# motorized_pinwheel.net
KiCad netlist of a schematic drawn in EAGLE
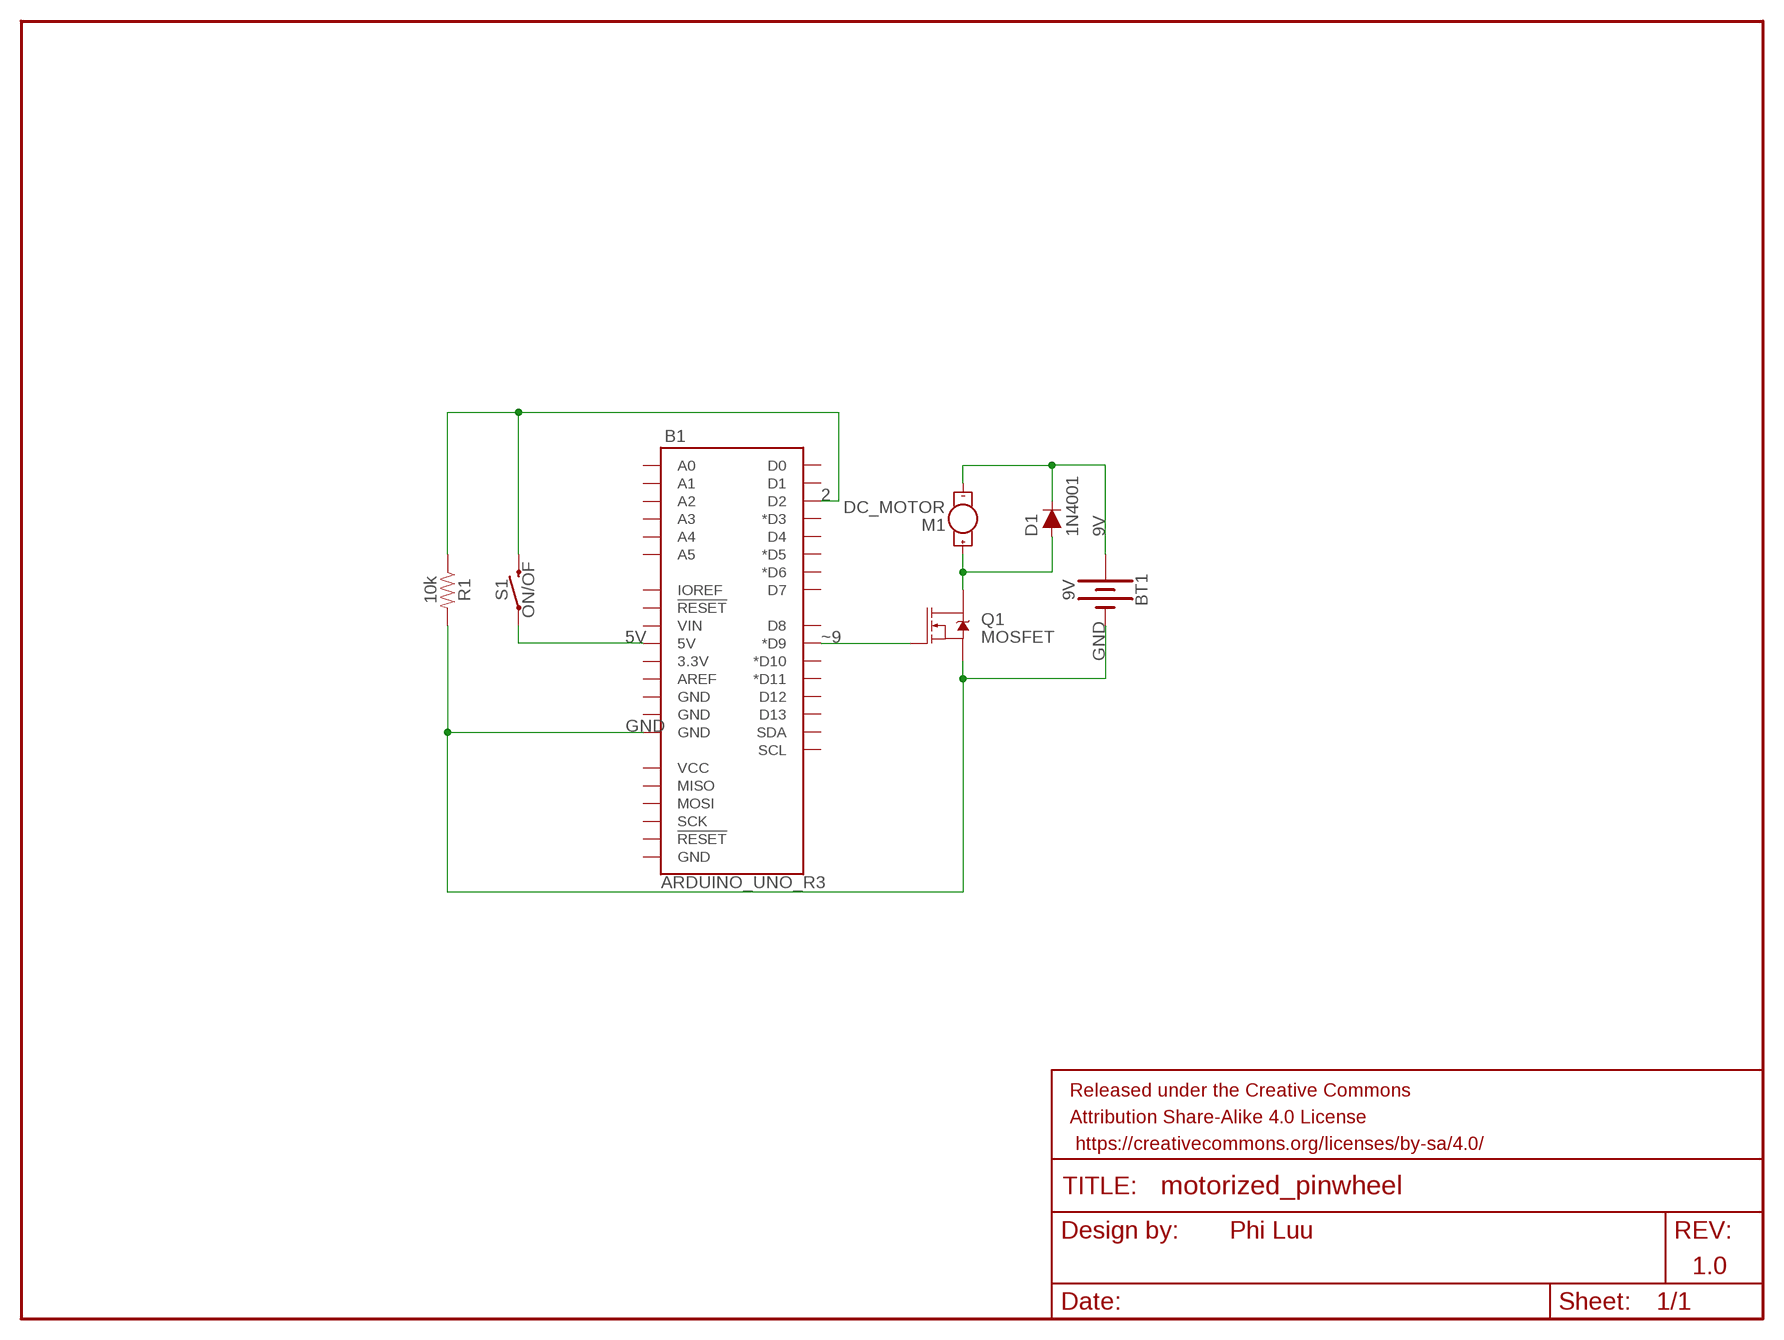
[diagram p0: schematic, sheet 1]

(export (version "E")
  (design (tool "Eeschema 10.0.6"))
  (components
    (comp (ref "B1")
      (value "ARDUINO_UNO_R3")
      (footprint "eagle-import:ARDUINO_R3")
      (libsource (lib "eagle-import") (part "ARDUINO_UNO_R3"))
    )
    (comp (ref "BT1")
      (value "9V")
      (footprint "eagle-import:BATTCON_9V")
      (libsource (lib "eagle-import") (part "BATTERY-9V"))
    )
    (comp (ref "D1")
      (value "1N4001")
      (footprint "eagle-import:DIODE-1N4001")
      (libsource (lib "eagle-import") (part "DIODE-PTH"))
    )
    (comp (ref "FRAME1")
      (value "FRAME-LETTER")
      (footprint "eagle-import:CREATIVE_COMMONS")
      (libsource (lib "eagle-import") (part "FRAME-LETTER"))
    )
    (comp (ref "M1")
      (value "DC_MOTOR")
      (footprint "eagle-import:VIBE-MOTOR-10MM")
      (libsource (lib "eagle-import") (part "MOTOR10MM"))
    )
    (comp (ref "Q1")
      (value "MOSFET")
      (footprint "eagle-import:TO220V")
      (libsource (lib "eagle-import") (part "MOSFET-NCH-FQP30N06L"))
    )
    (comp (ref "R1")
      (value "10k")
      (footprint "eagle-import:AXIAL-0.3")
      (libsource (lib "eagle-import") (part "10KOHM-HORIZ-1/4W-5%"))
    )
    (comp (ref "S1")
      (value "ON/OF")
      (footprint "eagle-import:TACTILE_SWITCH_PTH_6.0MM")
      (libsource (lib "eagle-import") (part "MOMENTARY-SWITCH-SPST-PTH-6.0MM"))
    )
  )
  (nets
    (net (code "1") (name "/2") (class "Default")
      (node (ref "B1") (pin "D2") (pinfunction "D2_D2") (pintype "bidirectional"))
      (node (ref "R1") (pin "P$1") (pinfunction "1_P$1") (pintype "passive"))
      (node (ref "S1") (pin "3") (pinfunction "2_3") (pintype "passive"))
    )
    (net (code "2") (name "/5V") (class "Default")
      (node (ref "B1") (pin "5V") (pinfunction "5V_5V") (pintype "bidirectional"))
      (node (ref "S1") (pin "1") (pinfunction "1_1") (pintype "passive"))
    )
    (net (code "3") (name "/9V") (class "Default")
      (node (ref "BT1") (pin "+") (pinfunction "+_+") (pintype "power_in"))
      (node (ref "D1") (pin "C") (pinfunction "C_C") (pintype "passive"))
      (node (ref "M1") (pin "-") (pinfunction "-_-") (pintype "bidirectional"))
    )
    (net (code "4") (name "/GND") (class "Default")
      (node (ref "B1") (pin "GND@2") (pinfunction "GND_GND@2") (pintype "bidirectional"))
      (node (ref "BT1") (pin "-") (pinfunction "-_-") (pintype "power_in"))
      (node (ref "Q1") (pin "3") (pinfunction "S_3") (pintype "bidirectional"))
      (node (ref "R1") (pin "P$2") (pinfunction "2_P$2") (pintype "passive"))
    )
    (net (code "5") (name "/~{9}") (class "Default")
      (node (ref "B1") (pin "D9") (pinfunction "*D9_D9") (pintype "bidirectional"))
      (node (ref "Q1") (pin "1") (pinfunction "G_1") (pintype "bidirectional"))
    )
    (net (code "6") (name "Net-(Q1-D)") (class "Default")
      (node (ref "D1") (pin "A") (pinfunction "A_A") (pintype "passive"))
      (node (ref "M1") (pin "+") (pinfunction "+_+") (pintype "bidirectional"))
      (node (ref "Q1") (pin "2") (pinfunction "D_2") (pintype "bidirectional"))
    )
    (net (code "7") (name "unconnected-(B1-*D3-PadD3)") (class "Default")
      (node (ref "B1") (pin "D3") (pinfunction "*D3_D3") (pintype "bidirectional"))
    )
    (net (code "8") (name "unconnected-(B1-*D5-PadD5)") (class "Default")
      (node (ref "B1") (pin "D5") (pinfunction "*D5_D5") (pintype "bidirectional"))
    )
    (net (code "9") (name "unconnected-(B1-*D6-PadD6)") (class "Default")
      (node (ref "B1") (pin "D6") (pinfunction "*D6_D6") (pintype "bidirectional"))
    )
    (net (code "10") (name "unconnected-(B1-*D10-PadD10)") (class "Default")
      (node (ref "B1") (pin "D10") (pinfunction "*D10_D10") (pintype "bidirectional"))
    )
    (net (code "11") (name "unconnected-(B1-*D11-PadD11)") (class "Default")
      (node (ref "B1") (pin "D11") (pinfunction "*D11_D11") (pintype "bidirectional"))
    )
    (net (code "12") (name "unconnected-(B1-GND-PadGND@1)") (class "Default")
      (node (ref "B1") (pin "GND@1") (pinfunction "GND_GND@1") (pintype "bidirectional"))
    )
    (net (code "13") (name "unconnected-(B1-GND-PadGND@3)") (class "Default")
      (node (ref "B1") (pin "GND@3") (pinfunction "GND_GND@3") (pintype "bidirectional"))
    )
    (net (code "14") (name "unconnected-(B1-GND-PadGND@4)") (class "Default")
      (node (ref "B1") (pin "GND@4") (pinfunction "GND_GND@4") (pintype "bidirectional"))
    )
    (net (code "15") (name "unconnected-(B1-Pad3.3V)") (class "Default")
      (node (ref "B1") (pin "3.3V") (pinfunction "3.3V_3.3V") (pintype "bidirectional"))
    )
    (net (code "16") (name "unconnected-(B1-PadA0)") (class "Default")
      (node (ref "B1") (pin "A0") (pinfunction "A0_A0") (pintype "bidirectional"))
    )
    (net (code "17") (name "unconnected-(B1-PadA1)") (class "Default")
      (node (ref "B1") (pin "A1") (pinfunction "A1_A1") (pintype "bidirectional"))
    )
    (net (code "18") (name "unconnected-(B1-PadA2)") (class "Default")
      (node (ref "B1") (pin "A2") (pinfunction "A2_A2") (pintype "bidirectional"))
    )
    (net (code "19") (name "unconnected-(B1-PadA3)") (class "Default")
      (node (ref "B1") (pin "A3") (pinfunction "A3_A3") (pintype "bidirectional"))
    )
    (net (code "20") (name "unconnected-(B1-PadA4)") (class "Default")
      (node (ref "B1") (pin "A4") (pinfunction "A4_A4") (pintype "bidirectional"))
    )
    (net (code "21") (name "unconnected-(B1-PadA5)") (class "Default")
      (node (ref "B1") (pin "A5") (pinfunction "A5_A5") (pintype "bidirectional"))
    )
    (net (code "22") (name "unconnected-(B1-PadAREF)") (class "Default")
      (node (ref "B1") (pin "AREF") (pinfunction "AREF_AREF") (pintype "bidirectional"))
    )
    (net (code "23") (name "unconnected-(B1-PadD0)") (class "Default")
      (node (ref "B1") (pin "D0") (pinfunction "D0_D0") (pintype "bidirectional"))
    )
    (net (code "24") (name "unconnected-(B1-PadD1)") (class "Default")
      (node (ref "B1") (pin "D1") (pinfunction "D1_D1") (pintype "bidirectional"))
    )
    (net (code "25") (name "unconnected-(B1-PadD4)") (class "Default")
      (node (ref "B1") (pin "D4") (pinfunction "D4_D4") (pintype "bidirectional"))
    )
    (net (code "26") (name "unconnected-(B1-PadD7)") (class "Default")
      (node (ref "B1") (pin "D7") (pinfunction "D7_D7") (pintype "bidirectional"))
    )
    (net (code "27") (name "unconnected-(B1-PadD8)") (class "Default")
      (node (ref "B1") (pin "D8") (pinfunction "D8_D8") (pintype "bidirectional"))
    )
    (net (code "28") (name "unconnected-(B1-PadD12)") (class "Default")
      (node (ref "B1") (pin "D12") (pinfunction "D12_D12") (pintype "bidirectional"))
    )
    (net (code "29") (name "unconnected-(B1-PadD13)") (class "Default")
      (node (ref "B1") (pin "D13") (pinfunction "D13_D13") (pintype "bidirectional"))
    )
    (net (code "30") (name "unconnected-(B1-PadIOREF)") (class "Default")
      (node (ref "B1") (pin "IOREF") (pinfunction "IOREF_IOREF") (pintype "bidirectional"))
    )
    (net (code "31") (name "unconnected-(B1-PadMISO)") (class "Default")
      (node (ref "B1") (pin "MISO") (pinfunction "MISO_MISO") (pintype "bidirectional"))
    )
    (net (code "32") (name "unconnected-(B1-PadMOSI)") (class "Default")
      (node (ref "B1") (pin "MOSI") (pinfunction "MOSI_MOSI") (pintype "bidirectional"))
    )
    (net (code "33") (name "unconnected-(B1-PadSCK)") (class "Default")
      (node (ref "B1") (pin "SCK") (pinfunction "SCK_SCK") (pintype "bidirectional"))
    )
    (net (code "34") (name "unconnected-(B1-PadSCL)") (class "Default")
      (node (ref "B1") (pin "SCL") (pinfunction "SCL_SCL") (pintype "bidirectional"))
    )
    (net (code "35") (name "unconnected-(B1-PadSDA)") (class "Default")
      (node (ref "B1") (pin "SDA") (pinfunction "SDA_SDA") (pintype "bidirectional"))
    )
    (net (code "36") (name "unconnected-(B1-PadVCC)") (class "Default")
      (node (ref "B1") (pin "VCC") (pinfunction "VCC_VCC") (pintype "bidirectional"))
    )
    (net (code "37") (name "unconnected-(B1-PadVIN)") (class "Default")
      (node (ref "B1") (pin "VIN") (pinfunction "VIN_VIN") (pintype "bidirectional"))
    )
    (net (code "38") (name "unconnected-(B1-~{RESET}-PadRESET@1)") (class "Default")
      (node (ref "B1") (pin "RESET@1") (pinfunction "~{RESET}_RESET@1") (pintype "bidirectional"))
    )
    (net (code "39") (name "unconnected-(B1-~{RESET}-PadRESET@2)") (class "Default")
      (node (ref "B1") (pin "RESET@2") (pinfunction "~{RESET}_RESET@2") (pintype "bidirectional"))
    )
  )
)
